# Arduino_Advanced_Sensor_Board.net
KiCad netlist of a schematic drawn in EAGLE
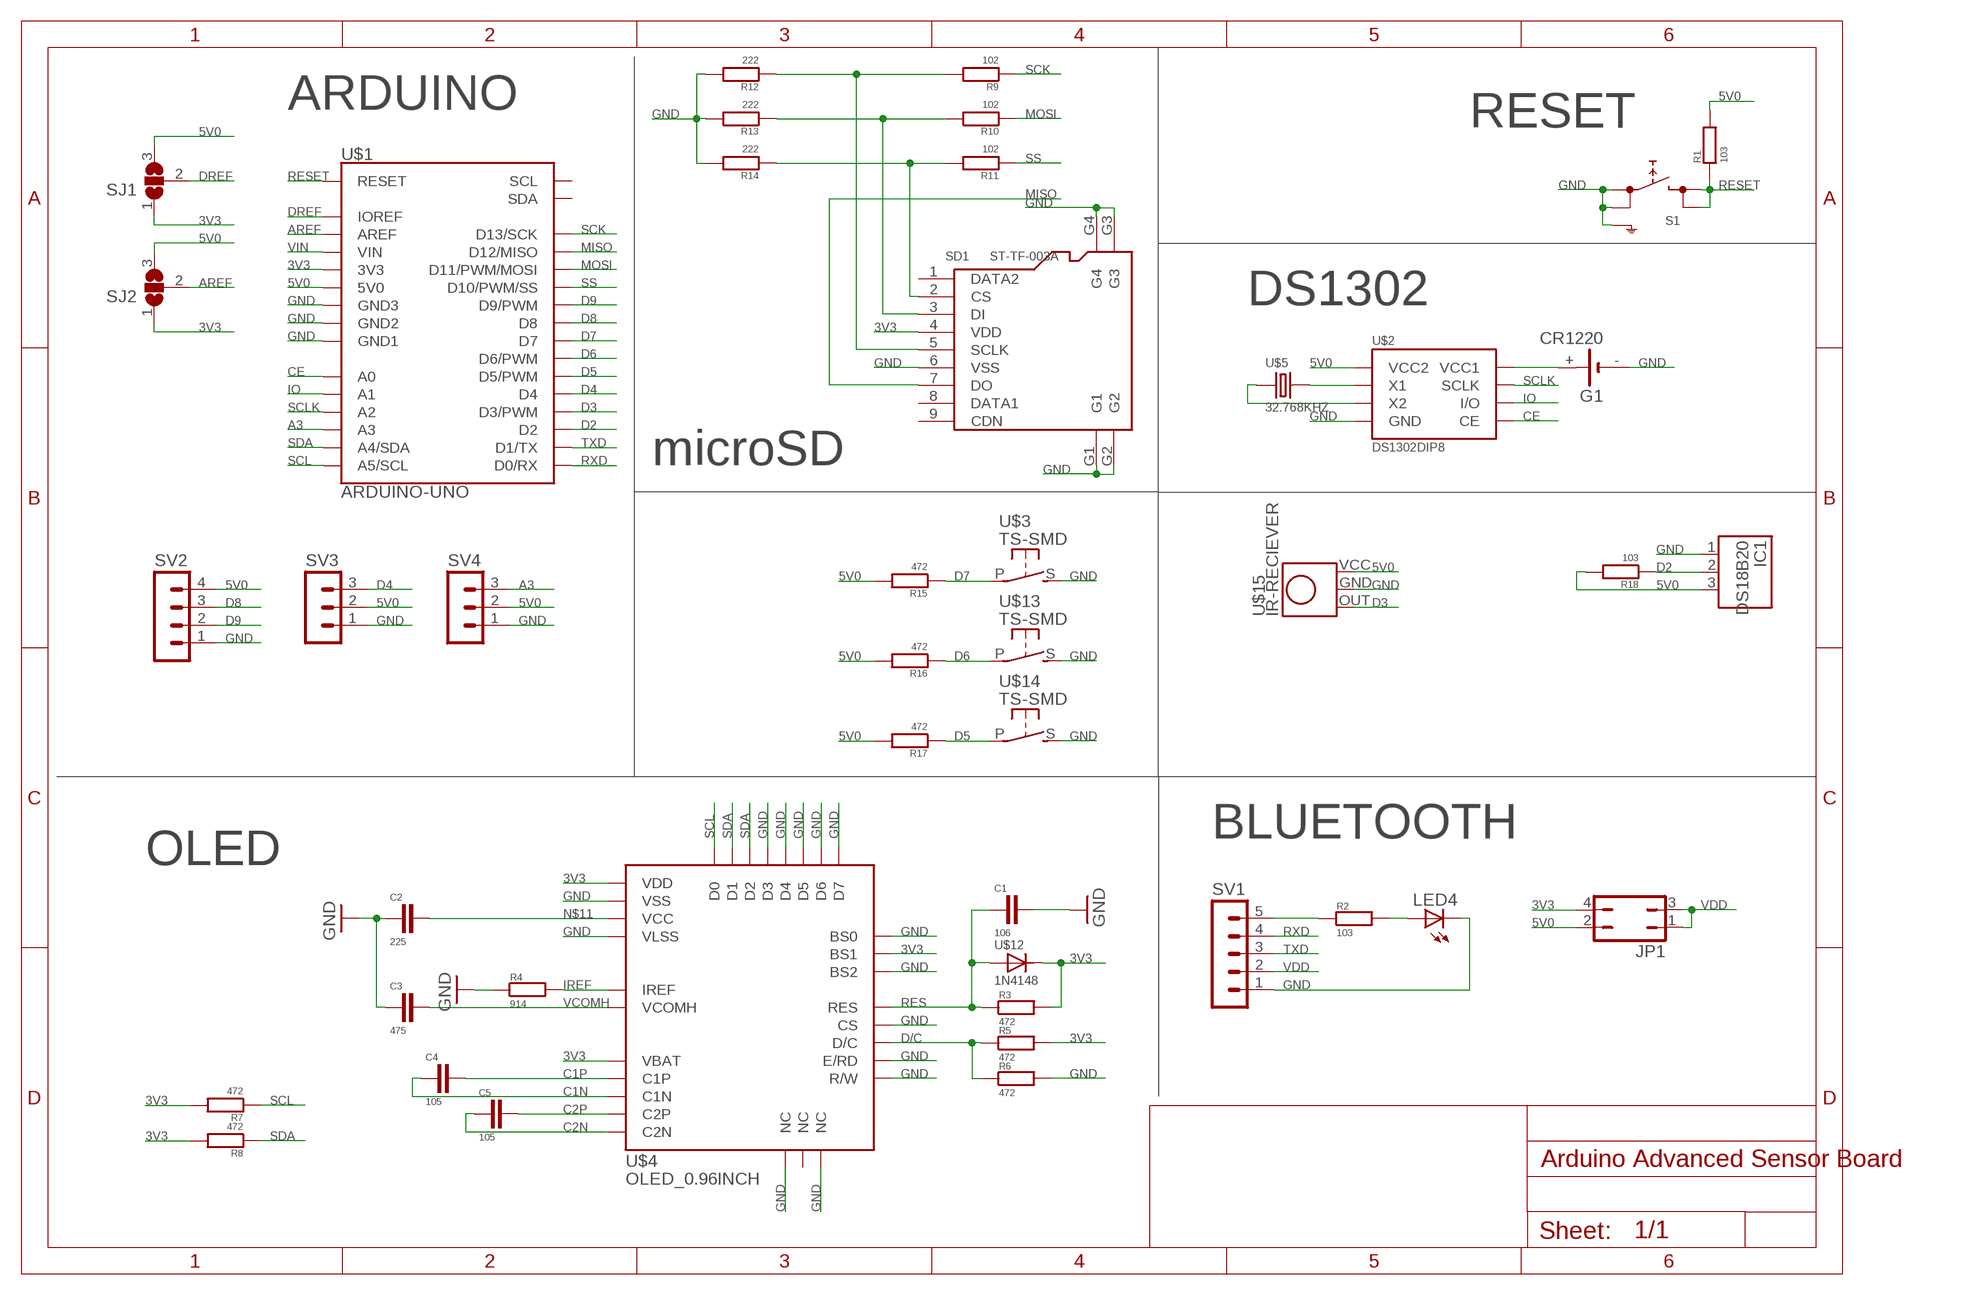
[diagram p0: schematic, sheet 1]

(export (version "E")
  (design (tool "Eeschema 10.0.6"))
  (components
    (comp (ref "C1")
      (value "106")
      (footprint "eagle-import:C0805")
      (libsource (lib "eagle-import") (part "C0805"))
    )
    (comp (ref "C2")
      (value "225")
      (footprint "eagle-import:C0805")
      (libsource (lib "eagle-import") (part "C0805"))
    )
    (comp (ref "C3")
      (value "475")
      (footprint "eagle-import:C0805")
      (libsource (lib "eagle-import") (part "C0805"))
    )
    (comp (ref "C4")
      (value "105")
      (footprint "eagle-import:C0805")
      (libsource (lib "eagle-import") (part "C0805"))
    )
    (comp (ref "C5")
      (value "105")
      (footprint "eagle-import:C0805")
      (libsource (lib "eagle-import") (part "C0805"))
    )
    (comp (ref "G1")
      (value "CR1220")
      (footprint "eagle-import:CR1220")
      (libsource (lib "eagle-import") (part "CR1220"))
    )
    (comp (ref "IC1")
      (value "DS18B20")
      (footprint "eagle-import:TO92")
      (libsource (lib "eagle-import") (part "DS18B20"))
    )
    (comp (ref "JP1")
      (value "JP2Q")
      (footprint "eagle-import:JP2Q")
      (libsource (lib "eagle-import") (part "JP2Q"))
    )
    (comp (ref "LED4")
      (value "LEDCHIPLED_0805")
      (footprint "eagle-import:LED0805")
      (libsource (lib "eagle-import") (part "LEDCHIPLED_0805"))
    )
    (comp (ref "R1")
      (value "103")
      (footprint "eagle-import:R0805")
      (libsource (lib "eagle-import") (part "R0805"))
    )
    (comp (ref "R2")
      (value "103")
      (footprint "eagle-import:R0805")
      (libsource (lib "eagle-import") (part "R0805"))
    )
    (comp (ref "R3")
      (value "472")
      (footprint "eagle-import:R0805")
      (libsource (lib "eagle-import") (part "R0805"))
    )
    (comp (ref "R4")
      (value "914")
      (footprint "eagle-import:R0805")
      (libsource (lib "eagle-import") (part "R0805"))
    )
    (comp (ref "R5")
      (value "472")
      (footprint "eagle-import:R0805")
      (libsource (lib "eagle-import") (part "R0805"))
    )
    (comp (ref "R6")
      (value "472")
      (footprint "eagle-import:R0805")
      (libsource (lib "eagle-import") (part "R0805"))
    )
    (comp (ref "R7")
      (value "472")
      (footprint "eagle-import:R0805")
      (libsource (lib "eagle-import") (part "R0805"))
    )
    (comp (ref "R8")
      (value "472")
      (footprint "eagle-import:R0805")
      (libsource (lib "eagle-import") (part "R0805"))
    )
    (comp (ref "R9")
      (value "102")
      (footprint "eagle-import:R0805")
      (libsource (lib "eagle-import") (part "R0805"))
    )
    (comp (ref "R10")
      (value "102")
      (footprint "eagle-import:R0805")
      (libsource (lib "eagle-import") (part "R0805"))
    )
    (comp (ref "R11")
      (value "102")
      (footprint "eagle-import:R0805")
      (libsource (lib "eagle-import") (part "R0805"))
    )
    (comp (ref "R12")
      (value "222")
      (footprint "eagle-import:R0805")
      (libsource (lib "eagle-import") (part "R0805"))
    )
    (comp (ref "R13")
      (value "222")
      (footprint "eagle-import:R0805")
      (libsource (lib "eagle-import") (part "R0805"))
    )
    (comp (ref "R14")
      (value "222")
      (footprint "eagle-import:R0805")
      (libsource (lib "eagle-import") (part "R0805"))
    )
    (comp (ref "R15")
      (value "472")
      (footprint "eagle-import:R0805")
      (libsource (lib "eagle-import") (part "R0805"))
    )
    (comp (ref "R16")
      (value "472")
      (footprint "eagle-import:R0805")
      (libsource (lib "eagle-import") (part "R0805"))
    )
    (comp (ref "R17")
      (value "472")
      (footprint "eagle-import:R0805")
      (libsource (lib "eagle-import") (part "R0805"))
    )
    (comp (ref "R18")
      (value "103")
      (footprint "eagle-import:R0805")
      (libsource (lib "eagle-import") (part "R0805"))
    )
    (comp (ref "S1")
      (value "TS-SMD_6S6_SHIELD")
      (footprint "eagle-import:TS-SMD_6_6_SHIELD")
      (libsource (lib "eagle-import") (part "TS-SMD_66_SHIELDS"))
    )
    (comp (ref "SD1")
      (value "ST-TF-003A")
      (footprint "eagle-import:MICRO-SD-SMD-9+4")
      (libsource (lib "eagle-import") (part "MICRO-SD-SMD-9+4"))
    )
    (comp (ref "SJ1")
      (value "SJ2W")
      (footprint "eagle-import:SJ_2")
      (libsource (lib "eagle-import") (part "SJ2W"))
    )
    (comp (ref "SJ2")
      (value "SJ2W")
      (footprint "eagle-import:SJ_2")
      (libsource (lib "eagle-import") (part "SJ2W"))
    )
    (comp (ref "SV1")
      (value "MA05-1")
      (footprint "eagle-import:MA05-1")
      (libsource (lib "eagle-import") (part "MA05-1"))
    )
    (comp (ref "SV2")
      (value "MA04-1")
      (footprint "eagle-import:MA04-1")
      (libsource (lib "eagle-import") (part "MA04-1"))
    )
    (comp (ref "SV3")
      (value "MA03-1")
      (footprint "eagle-import:MA03-1")
      (libsource (lib "eagle-import") (part "MA03-1"))
    )
    (comp (ref "SV4")
      (value "MA03-1")
      (footprint "eagle-import:MA03-1")
      (libsource (lib "eagle-import") (part "MA03-1"))
    )
    (comp (ref "U$1")
      (value "ARDUINO-UNO")
      (footprint "eagle-import:ARDUINO-UNO")
      (libsource (lib "eagle-import") (part "ARDUINO-UNO"))
    )
    (comp (ref "U$2")
      (value "DS1302DIP8")
      (footprint "eagle-import:DIP8")
      (libsource (lib "eagle-import") (part "DS1302DIP8"))
    )
    (comp (ref "U$3")
      (value "TS-SMD")
      (footprint "eagle-import:TS-SMD")
      (libsource (lib "eagle-import") (part "TS-SMD"))
    )
    (comp (ref "U$4")
      (value "OLED_0.96INCH")
      (footprint "eagle-import:OLED_0.96INCH")
      (libsource (lib "eagle-import") (part "OLED_0.96INCH"))
    )
    (comp (ref "U$5")
      (value "32.768KHZ")
      (footprint "eagle-import:32.768KHZ")
      (libsource (lib "eagle-import") (part "32.768KHZ"))
    )
    (comp (ref "U$12")
      (value "1N4148")
      (footprint "eagle-import:SOD123")
      (libsource (lib "eagle-import") (part "1N4148"))
    )
    (comp (ref "U$13")
      (value "TS-SMD")
      (footprint "eagle-import:TS-SMD")
      (libsource (lib "eagle-import") (part "TS-SMD"))
    )
    (comp (ref "U$14")
      (value "TS-SMD")
      (footprint "eagle-import:TS-SMD")
      (libsource (lib "eagle-import") (part "TS-SMD"))
    )
    (comp (ref "U$15")
      (value "IR-RECIEVER")
      (footprint "eagle-import:IR-RECIEVER")
      (libsource (lib "eagle-import") (part "IR-RECIEVER"))
    )
  )
  (nets
    (net (code "1") (name "/3V3") (class "Default")
      (node (ref "JP1") (pin "4") (pinfunction "4_4") (pintype "passive"))
      (node (ref "R3") (pin "2") (pinfunction "2_2") (pintype "bidirectional"))
      (node (ref "R5") (pin "2") (pinfunction "2_2") (pintype "bidirectional"))
      (node (ref "R7") (pin "2") (pinfunction "2_2") (pintype "bidirectional"))
      (node (ref "R8") (pin "2") (pinfunction "2_2") (pintype "bidirectional"))
      (node (ref "SD1") (pin "4") (pinfunction "VDD_4") (pintype "bidirectional"))
      (node (ref "SJ1") (pin "1") (pinfunction "1_1") (pintype "passive"))
      (node (ref "SJ2") (pin "1") (pinfunction "1_1") (pintype "passive"))
      (node (ref "U$1") (pin "3V3") (pinfunction "3V3_3V3") (pintype "bidirectional"))
      (node (ref "U$12") (pin "1") (pinfunction "1_1") (pintype "bidirectional"))
      (node (ref "U$4") (pin "11") (pinfunction "BS1_11") (pintype "bidirectional"))
      (node (ref "U$4") (pin "6") (pinfunction "VBAT_6") (pintype "bidirectional"))
      (node (ref "U$4") (pin "9") (pinfunction "VDD_9") (pintype "bidirectional"))
    )
    (net (code "2") (name "/5V0") (class "Default")
      (node (ref "IC1") (pin "3") (pinfunction "VCC_3") (pintype "bidirectional"))
      (node (ref "JP1") (pin "2") (pinfunction "2_2") (pintype "passive"))
      (node (ref "R1") (pin "2") (pinfunction "2_2") (pintype "bidirectional"))
      (node (ref "R15") (pin "2") (pinfunction "2_2") (pintype "bidirectional"))
      (node (ref "R16") (pin "2") (pinfunction "2_2") (pintype "bidirectional"))
      (node (ref "R17") (pin "2") (pinfunction "2_2") (pintype "bidirectional"))
      (node (ref "R18") (pin "2") (pinfunction "2_2") (pintype "bidirectional"))
      (node (ref "SJ1") (pin "3") (pinfunction "3_3") (pintype "passive"))
      (node (ref "SJ2") (pin "3") (pinfunction "3_3") (pintype "passive"))
      (node (ref "SV2") (pin "4") (pinfunction "4_4") (pintype "passive"))
      (node (ref "SV3") (pin "2") (pinfunction "2_2") (pintype "passive"))
      (node (ref "SV4") (pin "2") (pinfunction "2_2") (pintype "passive"))
      (node (ref "U$1") (pin "5V0") (pinfunction "5V0_5V0") (pintype "bidirectional"))
      (node (ref "U$15") (pin "VCC") (pinfunction "VCC_VCC") (pintype "bidirectional"))
      (node (ref "U$2") (pin "1") (pinfunction "VCC2_1") (pintype "bidirectional"))
    )
    (net (code "3") (name "/A3") (class "Default")
      (node (ref "SV4") (pin "3") (pinfunction "3_3") (pintype "passive"))
      (node (ref "U$1") (pin "A3") (pinfunction "A3_A3") (pintype "bidirectional"))
    )
    (net (code "4") (name "/AREF") (class "Default")
      (node (ref "SJ2") (pin "2") (pinfunction "2_2") (pintype "passive"))
      (node (ref "U$1") (pin "AREF") (pinfunction "AREF_AREF") (pintype "bidirectional"))
    )
    (net (code "5") (name "/C1N") (class "Default")
      (node (ref "C4") (pin "2") (pinfunction "2_2") (pintype "bidirectional"))
      (node (ref "U$4") (pin "5") (pinfunction "C1N_5") (pintype "bidirectional"))
    )
    (net (code "6") (name "/C1P") (class "Default")
      (node (ref "C4") (pin "1") (pinfunction "1_1") (pintype "bidirectional"))
      (node (ref "U$4") (pin "4") (pinfunction "C1P_4") (pintype "bidirectional"))
    )
    (net (code "7") (name "/C2N") (class "Default")
      (node (ref "C5") (pin "2") (pinfunction "2_2") (pintype "bidirectional"))
      (node (ref "U$4") (pin "3") (pinfunction "C2N_3") (pintype "bidirectional"))
    )
    (net (code "8") (name "/C2P") (class "Default")
      (node (ref "C5") (pin "1") (pinfunction "1_1") (pintype "bidirectional"))
      (node (ref "U$4") (pin "2") (pinfunction "C2P_2") (pintype "bidirectional"))
    )
    (net (code "9") (name "/CE") (class "Default")
      (node (ref "U$1") (pin "A0") (pinfunction "A0_A0") (pintype "bidirectional"))
      (node (ref "U$2") (pin "5") (pinfunction "CE_5") (pintype "bidirectional"))
    )
    (net (code "10") (name "/D2") (class "Default")
      (node (ref "IC1") (pin "2") (pinfunction "DQ_2") (pintype "bidirectional"))
      (node (ref "R18") (pin "1") (pinfunction "1_1") (pintype "bidirectional"))
      (node (ref "U$1") (pin "D2") (pinfunction "D2_D2") (pintype "bidirectional"))
    )
    (net (code "11") (name "/D3") (class "Default")
      (node (ref "U$1") (pin "D3") (pinfunction "D3/PWM_D3") (pintype "bidirectional"))
      (node (ref "U$15") (pin "OUT") (pinfunction "OUT_OUT") (pintype "bidirectional"))
    )
    (net (code "12") (name "/D4") (class "Default")
      (node (ref "SV3") (pin "3") (pinfunction "3_3") (pintype "passive"))
      (node (ref "U$1") (pin "D4") (pinfunction "D4_D4") (pintype "bidirectional"))
    )
    (net (code "13") (name "/D5") (class "Default")
      (node (ref "R17") (pin "1") (pinfunction "1_1") (pintype "bidirectional"))
      (node (ref "U$1") (pin "D5") (pinfunction "D5/PWM_D5") (pintype "bidirectional"))
      (node (ref "U$14") (pin "P") (pinfunction "P_P") (pintype "passive"))
    )
    (net (code "14") (name "/D6") (class "Default")
      (node (ref "R16") (pin "1") (pinfunction "1_1") (pintype "bidirectional"))
      (node (ref "U$1") (pin "D6") (pinfunction "D6/PWM_D6") (pintype "bidirectional"))
      (node (ref "U$13") (pin "P") (pinfunction "P_P") (pintype "passive"))
    )
    (net (code "15") (name "/D7") (class "Default")
      (node (ref "R15") (pin "1") (pinfunction "1_1") (pintype "bidirectional"))
      (node (ref "U$1") (pin "D7") (pinfunction "D7_D7") (pintype "bidirectional"))
      (node (ref "U$3") (pin "P") (pinfunction "P_P") (pintype "passive"))
    )
    (net (code "16") (name "/D8") (class "Default")
      (node (ref "SV2") (pin "3") (pinfunction "3_3") (pintype "passive"))
      (node (ref "U$1") (pin "D8") (pinfunction "D8_D8") (pintype "bidirectional"))
    )
    (net (code "17") (name "/D9") (class "Default")
      (node (ref "SV2") (pin "2") (pinfunction "2_2") (pintype "passive"))
      (node (ref "U$1") (pin "D9") (pinfunction "D9/PWM_D9") (pintype "bidirectional"))
    )
    (net (code "18") (name "/DREF") (class "Default")
      (node (ref "SJ1") (pin "2") (pinfunction "2_2") (pintype "passive"))
      (node (ref "U$1") (pin "REF") (pinfunction "IOREF_REF") (pintype "bidirectional"))
    )
    (net (code "19") (name "/D{slash}C") (class "Default")
      (node (ref "R5") (pin "1") (pinfunction "1_1") (pintype "bidirectional"))
      (node (ref "R6") (pin "1") (pinfunction "1_1") (pintype "bidirectional"))
      (node (ref "U$4") (pin "15") (pinfunction "D/C_15") (pintype "bidirectional"))
    )
    (net (code "20") (name "/IO") (class "Default")
      (node (ref "U$1") (pin "A1") (pinfunction "A1_A1") (pintype "bidirectional"))
      (node (ref "U$2") (pin "6") (pinfunction "I/O_6") (pintype "bidirectional"))
    )
    (net (code "21") (name "/IREF") (class "Default")
      (node (ref "R4") (pin "2") (pinfunction "2_2") (pintype "bidirectional"))
      (node (ref "U$4") (pin "26") (pinfunction "IREF_26") (pintype "bidirectional"))
    )
    (net (code "22") (name "/MISO") (class "Default")
      (node (ref "SD1") (pin "7") (pinfunction "DO_7") (pintype "bidirectional"))
      (node (ref "U$1") (pin "D12") (pinfunction "D12/MISO_D12") (pintype "bidirectional"))
    )
    (net (code "23") (name "/MOSI") (class "Default")
      (node (ref "R10") (pin "1") (pinfunction "1_1") (pintype "bidirectional"))
      (node (ref "U$1") (pin "D11") (pinfunction "D11/PWM/MOSI_D11") (pintype "bidirectional"))
    )
    (net (code "24") (name "/N$11") (class "Default")
      (node (ref "C2") (pin "1") (pinfunction "1_1") (pintype "bidirectional"))
      (node (ref "U$4") (pin "28") (pinfunction "VCC_28") (pintype "bidirectional"))
    )
    (net (code "25") (name "/RES") (class "Default")
      (node (ref "C1") (pin "2") (pinfunction "2_2") (pintype "bidirectional"))
      (node (ref "R3") (pin "1") (pinfunction "1_1") (pintype "bidirectional"))
      (node (ref "U$12") (pin "2") (pinfunction "2_2") (pintype "bidirectional"))
      (node (ref "U$4") (pin "14") (pinfunction "RES_14") (pintype "bidirectional"))
    )
    (net (code "26") (name "/RESET") (class "Default")
      (node (ref "R1") (pin "1") (pinfunction "1_1") (pintype "bidirectional"))
      (node (ref "S1") (pin "3") (pinfunction "2.1_3") (pintype "passive"))
      (node (ref "S1") (pin "4") (pinfunction "2.2_4") (pintype "passive"))
      (node (ref "U$1") (pin "RST") (pinfunction "RESET_RST") (pintype "bidirectional"))
    )
    (net (code "27") (name "/RXD") (class "Default")
      (node (ref "SV1") (pin "4") (pinfunction "4_4") (pintype "passive"))
      (node (ref "U$1") (pin "D0") (pinfunction "D0/RX_D0") (pintype "bidirectional"))
    )
    (net (code "28") (name "/SCK") (class "Default")
      (node (ref "R9") (pin "1") (pinfunction "1_1") (pintype "bidirectional"))
      (node (ref "U$1") (pin "D13") (pinfunction "D13/SCK_D13") (pintype "bidirectional"))
    )
    (net (code "29") (name "/SCL") (class "Default")
      (node (ref "R7") (pin "1") (pinfunction "1_1") (pintype "bidirectional"))
      (node (ref "U$1") (pin "A5") (pinfunction "A5/SCL_A5") (pintype "bidirectional"))
      (node (ref "U$4") (pin "18") (pinfunction "D0_18") (pintype "bidirectional"))
    )
    (net (code "30") (name "/SCLK") (class "Default")
      (node (ref "U$1") (pin "A2") (pinfunction "A2_A2") (pintype "bidirectional"))
      (node (ref "U$2") (pin "7") (pinfunction "SCLK_7") (pintype "bidirectional"))
    )
    (net (code "31") (name "/SDA") (class "Default")
      (node (ref "R8") (pin "1") (pinfunction "1_1") (pintype "bidirectional"))
      (node (ref "U$1") (pin "A4") (pinfunction "A4/SDA_A4") (pintype "bidirectional"))
      (node (ref "U$4") (pin "19") (pinfunction "D1_19") (pintype "bidirectional"))
      (node (ref "U$4") (pin "20") (pinfunction "D2_20") (pintype "bidirectional"))
    )
    (net (code "32") (name "/SS") (class "Default")
      (node (ref "R11") (pin "1") (pinfunction "1_1") (pintype "bidirectional"))
      (node (ref "U$1") (pin "D10") (pinfunction "D10/PWM/SS_D10") (pintype "bidirectional"))
    )
    (net (code "33") (name "/TXD") (class "Default")
      (node (ref "SV1") (pin "3") (pinfunction "3_3") (pintype "passive"))
      (node (ref "U$1") (pin "D1") (pinfunction "D1/TX_D1") (pintype "bidirectional"))
    )
    (net (code "34") (name "/VCOMH") (class "Default")
      (node (ref "C3") (pin "1") (pinfunction "1_1") (pintype "bidirectional"))
      (node (ref "U$4") (pin "27") (pinfunction "VCOMH_27") (pintype "bidirectional"))
    )
    (net (code "35") (name "/VDD") (class "Default")
      (node (ref "JP1") (pin "1") (pinfunction "1_1") (pintype "passive"))
      (node (ref "JP1") (pin "3") (pinfunction "3_3") (pintype "passive"))
      (node (ref "SV1") (pin "2") (pinfunction "2_2") (pintype "passive"))
    )
    (net (code "36") (name "/VIN") (class "Default")
      (node (ref "U$1") (pin "VIN") (pinfunction "VIN_VIN") (pintype "bidirectional"))
    )
    (net (code "37") (name "GND") (class "Default")
      (node (ref "C1") (pin "1") (pinfunction "1_1") (pintype "bidirectional"))
      (node (ref "C2") (pin "2") (pinfunction "2_2") (pintype "bidirectional"))
      (node (ref "C3") (pin "2") (pinfunction "2_2") (pintype "bidirectional"))
      (node (ref "G1") (pin "-") (pinfunction "-_-") (pintype "passive"))
      (node (ref "IC1") (pin "1") (pinfunction "GND_1") (pintype "bidirectional"))
      (node (ref "LED4") (pin "C") (pinfunction "C_C") (pintype "passive"))
      (node (ref "R12") (pin "2") (pinfunction "2_2") (pintype "bidirectional"))
      (node (ref "R13") (pin "2") (pinfunction "2_2") (pintype "bidirectional"))
      (node (ref "R14") (pin "2") (pinfunction "2_2") (pintype "bidirectional"))
      (node (ref "R4") (pin "1") (pinfunction "1_1") (pintype "bidirectional"))
      (node (ref "R6") (pin "2") (pinfunction "2_2") (pintype "bidirectional"))
      (node (ref "S1") (pin "1") (pinfunction "1.1_1") (pintype "passive"))
      (node (ref "S1") (pin "2") (pinfunction "1.2_2") (pintype "passive"))
      (node (ref "S1") (pin "5") (pinfunction "SH_5") (pintype "passive"))
      (node (ref "SD1") (pin "6") (pinfunction "VSS_6") (pintype "bidirectional"))
      (node (ref "SD1") (pin "G1") (pinfunction "G1_G1") (pintype "bidirectional"))
      (node (ref "SD1") (pin "G2") (pinfunction "G2_G2") (pintype "bidirectional"))
      (node (ref "SD1") (pin "G3") (pinfunction "G3_G3") (pintype "bidirectional"))
      (node (ref "SD1") (pin "G4") (pinfunction "G4_G4") (pintype "bidirectional"))
      (node (ref "SV1") (pin "1") (pinfunction "1_1") (pintype "passive"))
      (node (ref "SV2") (pin "1") (pinfunction "1_1") (pintype "passive"))
      (node (ref "SV3") (pin "1") (pinfunction "1_1") (pintype "passive"))
      (node (ref "SV4") (pin "1") (pinfunction "1_1") (pintype "passive"))
      (node (ref "U$1") (pin "GND1") (pinfunction "GND1_GND1") (pintype "bidirectional"))
      (node (ref "U$1") (pin "GND2") (pinfunction "GND2_GND2") (pintype "bidirectional"))
      (node (ref "U$1") (pin "GND3") (pinfunction "GND3_GND3") (pintype "bidirectional"))
      (node (ref "U$13") (pin "S") (pinfunction "S_S") (pintype "passive"))
      (node (ref "U$14") (pin "S") (pinfunction "S_S") (pintype "passive"))
      (node (ref "U$15") (pin "GND") (pinfunction "GND_GND") (pintype "bidirectional"))
      (node (ref "U$2") (pin "4") (pinfunction "GND_4") (pintype "bidirectional"))
      (node (ref "U$3") (pin "S") (pinfunction "S_S") (pintype "passive"))
      (node (ref "U$4") (pin "1") (pinfunction "NC_1") (pintype "bidirectional"))
      (node (ref "U$4") (pin "10") (pinfunction "BS0_10") (pintype "bidirectional"))
      (node (ref "U$4") (pin "12") (pinfunction "BS2_12") (pintype "bidirectional"))
      (node (ref "U$4") (pin "13") (pinfunction "CS_13") (pintype "bidirectional"))
      (node (ref "U$4") (pin "16") (pinfunction "R/W_16") (pintype "bidirectional"))
      (node (ref "U$4") (pin "17") (pinfunction "E/RD_17") (pintype "bidirectional"))
      (node (ref "U$4") (pin "21") (pinfunction "D3_21") (pintype "bidirectional"))
      (node (ref "U$4") (pin "22") (pinfunction "D4_22") (pintype "bidirectional"))
      (node (ref "U$4") (pin "23") (pinfunction "D5_23") (pintype "bidirectional"))
      (node (ref "U$4") (pin "24") (pinfunction "D6_24") (pintype "bidirectional"))
      (node (ref "U$4") (pin "25") (pinfunction "D7_25") (pintype "bidirectional"))
      (node (ref "U$4") (pin "29") (pinfunction "VLSS_29") (pintype "bidirectional"))
      (node (ref "U$4") (pin "30") (pinfunction "NC_30") (pintype "bidirectional"))
      (node (ref "U$4") (pin "8") (pinfunction "VSS_8") (pintype "bidirectional"))
    )
    (net (code "38") (name "Net-(LED4-PadA)") (class "Default")
      (node (ref "LED4") (pin "A") (pinfunction "A_A") (pintype "passive"))
      (node (ref "R2") (pin "2") (pinfunction "2_2") (pintype "bidirectional"))
    )
    (net (code "39") (name "Net-(R2-Pad1)") (class "Default")
      (node (ref "R2") (pin "1") (pinfunction "1_1") (pintype "bidirectional"))
      (node (ref "SV1") (pin "5") (pinfunction "5_5") (pintype "passive"))
    )
    (net (code "40") (name "Net-(SD1-CS)") (class "Default")
      (node (ref "R11") (pin "2") (pinfunction "2_2") (pintype "bidirectional"))
      (node (ref "R14") (pin "1") (pinfunction "1_1") (pintype "bidirectional"))
      (node (ref "SD1") (pin "2") (pinfunction "CS_2") (pintype "bidirectional"))
    )
    (net (code "41") (name "Net-(SD1-DI)") (class "Default")
      (node (ref "R10") (pin "2") (pinfunction "2_2") (pintype "bidirectional"))
      (node (ref "R13") (pin "1") (pinfunction "1_1") (pintype "bidirectional"))
      (node (ref "SD1") (pin "3") (pinfunction "DI_3") (pintype "bidirectional"))
    )
    (net (code "42") (name "Net-(SD1-SCLK)") (class "Default")
      (node (ref "R12") (pin "1") (pinfunction "1_1") (pintype "bidirectional"))
      (node (ref "R9") (pin "2") (pinfunction "2_2") (pintype "bidirectional"))
      (node (ref "SD1") (pin "5") (pinfunction "SCLK_5") (pintype "bidirectional"))
    )
    (net (code "43") (name "Net-(U$2-VCC1)") (class "Default")
      (node (ref "G1") (pin "+") (pinfunction "+_+") (pintype "passive"))
      (node (ref "U$2") (pin "8") (pinfunction "VCC1_8") (pintype "bidirectional"))
    )
    (net (code "44") (name "Net-(U$2-X1)") (class "Default")
      (node (ref "U$2") (pin "2") (pinfunction "X1_2") (pintype "bidirectional"))
      (node (ref "U$5") (pin "P$2") (pinfunction "2_P$2") (pintype "passive"))
    )
    (net (code "45") (name "Net-(U$2-X2)") (class "Default")
      (node (ref "U$2") (pin "3") (pinfunction "X2_3") (pintype "bidirectional"))
      (node (ref "U$5") (pin "P$1") (pinfunction "1_P$1") (pintype "passive"))
    )
    (net (code "46") (name "unconnected-(SD1-CDN-Pad9)") (class "Default")
      (node (ref "SD1") (pin "9") (pinfunction "CDN_9") (pintype "bidirectional"))
    )
    (net (code "47") (name "unconnected-(SD1-DATA1-Pad8)") (class "Default")
      (node (ref "SD1") (pin "8") (pinfunction "DATA1_8") (pintype "bidirectional"))
    )
    (net (code "48") (name "unconnected-(SD1-DATA2-Pad1)") (class "Default")
      (node (ref "SD1") (pin "1") (pinfunction "DATA2_1") (pintype "bidirectional"))
    )
    (net (code "49") (name "unconnected-(U$1-PadSCL)") (class "Default")
      (node (ref "U$1") (pin "SCL") (pinfunction "SCL_SCL") (pintype "bidirectional"))
    )
    (net (code "50") (name "unconnected-(U$1-PadSDA)") (class "Default")
      (node (ref "U$1") (pin "SDA") (pinfunction "SDA_SDA") (pintype "bidirectional"))
    )
    (net (code "51") (name "unconnected-(U$4-NC-Pad7)") (class "Default")
      (node (ref "U$4") (pin "7") (pinfunction "NC_7") (pintype "bidirectional"))
    )
  )
)
